# controller3.net
KiCad netlist of a schematic drawn in EAGLE
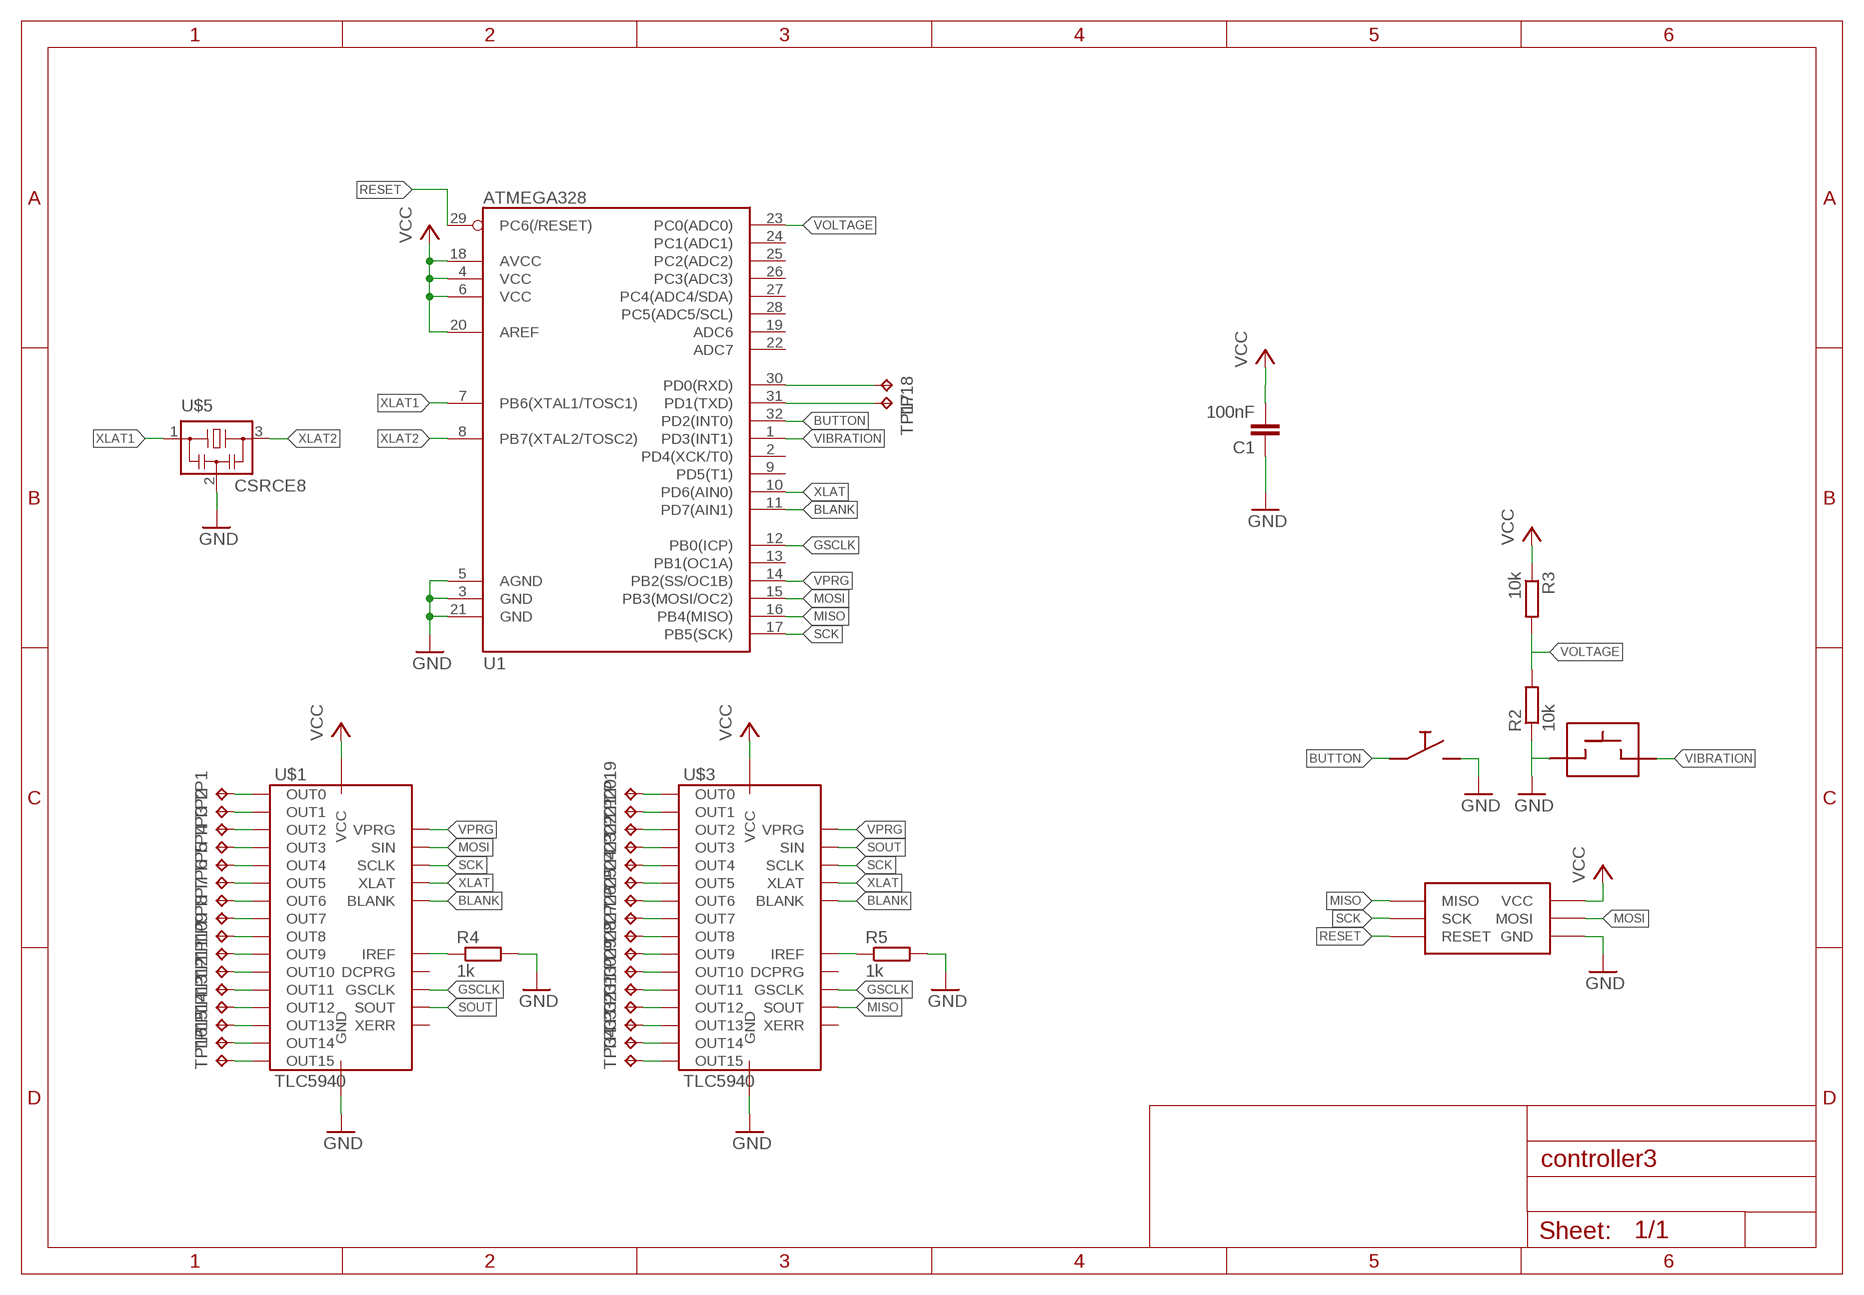
[diagram p0: schematic, sheet 1]

(export (version "E")
  (design (tool "Eeschema 10.0.6"))
  (components
    (comp (ref "C1")
      (value "100nF")
      (footprint "eagle-import:C0603")
      (libsource (lib "eagle-import") (part "C-EUC0603"))
    )
    (comp (ref "R2")
      (value "10k")
      (footprint "eagle-import:R0603")
      (libsource (lib "eagle-import") (part "R-EU_R0603"))
    )
    (comp (ref "R3")
      (value "10k")
      (footprint "eagle-import:R0603")
      (libsource (lib "eagle-import") (part "R-EU_R0603"))
    )
    (comp (ref "R4")
      (value "1k")
      (footprint "eagle-import:R0603")
      (libsource (lib "eagle-import") (part "R-EU_R0603"))
    )
    (comp (ref "R5")
      (value "1k")
      (footprint "eagle-import:R0603")
      (libsource (lib "eagle-import") (part "R-EU_R0603"))
    )
    (comp (ref "TP1")
      (value "TPTP15SQ")
      (footprint "eagle-import:TP15SQ")
      (libsource (lib "eagle-import") (part "TPTP15SQ"))
    )
    (comp (ref "TP2")
      (value "TPTP15SQ")
      (footprint "eagle-import:TP15SQ")
      (libsource (lib "eagle-import") (part "TPTP15SQ"))
    )
    (comp (ref "TP3")
      (value "TPTP15SQ")
      (footprint "eagle-import:TP15SQ")
      (libsource (lib "eagle-import") (part "TPTP15SQ"))
    )
    (comp (ref "TP4")
      (value "TPTP15SQ")
      (footprint "eagle-import:TP15SQ")
      (libsource (lib "eagle-import") (part "TPTP15SQ"))
    )
    (comp (ref "TP5")
      (value "TPTP15SQ")
      (footprint "eagle-import:TP15SQ")
      (libsource (lib "eagle-import") (part "TPTP15SQ"))
    )
    (comp (ref "TP6")
      (value "TPTP15SQ")
      (footprint "eagle-import:TP15SQ")
      (libsource (lib "eagle-import") (part "TPTP15SQ"))
    )
    (comp (ref "TP7")
      (value "TPTP15SQ")
      (footprint "eagle-import:TP15SQ")
      (libsource (lib "eagle-import") (part "TPTP15SQ"))
    )
    (comp (ref "TP8")
      (value "TPTP15SQ")
      (footprint "eagle-import:TP15SQ")
      (libsource (lib "eagle-import") (part "TPTP15SQ"))
    )
    (comp (ref "TP9")
      (value "TPTP15SQ")
      (footprint "eagle-import:TP15SQ")
      (libsource (lib "eagle-import") (part "TPTP15SQ"))
    )
    (comp (ref "TP10")
      (value "TPTP15SQ")
      (footprint "eagle-import:TP15SQ")
      (libsource (lib "eagle-import") (part "TPTP15SQ"))
    )
    (comp (ref "TP11")
      (value "TPTP15SQ")
      (footprint "eagle-import:TP15SQ")
      (libsource (lib "eagle-import") (part "TPTP15SQ"))
    )
    (comp (ref "TP12")
      (value "TPTP15SQ")
      (footprint "eagle-import:TP15SQ")
      (libsource (lib "eagle-import") (part "TPTP15SQ"))
    )
    (comp (ref "TP13")
      (value "TPTP15SQ")
      (footprint "eagle-import:TP15SQ")
      (libsource (lib "eagle-import") (part "TPTP15SQ"))
    )
    (comp (ref "TP14")
      (value "TPTP15SQ")
      (footprint "eagle-import:TP15SQ")
      (libsource (lib "eagle-import") (part "TPTP15SQ"))
    )
    (comp (ref "TP15")
      (value "TPTP15SQ")
      (footprint "eagle-import:TP15SQ")
      (libsource (lib "eagle-import") (part "TPTP15SQ"))
    )
    (comp (ref "TP16")
      (value "TPTP15SQ")
      (footprint "eagle-import:TP15SQ")
      (libsource (lib "eagle-import") (part "TPTP15SQ"))
    )
    (comp (ref "TP17")
      (value "TPTP15SQ")
      (footprint "eagle-import:TP15SQ")
      (libsource (lib "eagle-import") (part "TPTP15SQ"))
    )
    (comp (ref "TP18")
      (value "TPTP15SQ")
      (footprint "eagle-import:TP15SQ")
      (libsource (lib "eagle-import") (part "TPTP15SQ"))
    )
    (comp (ref "TP19")
      (value "TPTP15SQ")
      (footprint "eagle-import:TP15SQ")
      (libsource (lib "eagle-import") (part "TPTP15SQ"))
    )
    (comp (ref "TP20")
      (value "TPTP15SQ")
      (footprint "eagle-import:TP15SQ")
      (libsource (lib "eagle-import") (part "TPTP15SQ"))
    )
    (comp (ref "TP21")
      (value "TPTP15SQ")
      (footprint "eagle-import:TP15SQ")
      (libsource (lib "eagle-import") (part "TPTP15SQ"))
    )
    (comp (ref "TP22")
      (value "TPTP15SQ")
      (footprint "eagle-import:TP15SQ")
      (libsource (lib "eagle-import") (part "TPTP15SQ"))
    )
    (comp (ref "TP23")
      (value "TPTP15SQ")
      (footprint "eagle-import:TP15SQ")
      (libsource (lib "eagle-import") (part "TPTP15SQ"))
    )
    (comp (ref "TP24")
      (value "TPTP15SQ")
      (footprint "eagle-import:TP15SQ")
      (libsource (lib "eagle-import") (part "TPTP15SQ"))
    )
    (comp (ref "TP25")
      (value "TPTP15SQ")
      (footprint "eagle-import:TP15SQ")
      (libsource (lib "eagle-import") (part "TPTP15SQ"))
    )
    (comp (ref "TP26")
      (value "TPTP15SQ")
      (footprint "eagle-import:TP15SQ")
      (libsource (lib "eagle-import") (part "TPTP15SQ"))
    )
    (comp (ref "TP27")
      (value "TPTP15SQ")
      (footprint "eagle-import:TP15SQ")
      (libsource (lib "eagle-import") (part "TPTP15SQ"))
    )
    (comp (ref "TP28")
      (value "TPTP15SQ")
      (footprint "eagle-import:TP15SQ")
      (libsource (lib "eagle-import") (part "TPTP15SQ"))
    )
    (comp (ref "TP29")
      (value "TPTP15SQ")
      (footprint "eagle-import:TP15SQ")
      (libsource (lib "eagle-import") (part "TPTP15SQ"))
    )
    (comp (ref "TP30")
      (value "TPTP15SQ")
      (footprint "eagle-import:TP15SQ")
      (libsource (lib "eagle-import") (part "TPTP15SQ"))
    )
    (comp (ref "TP31")
      (value "TPTP15SQ")
      (footprint "eagle-import:TP15SQ")
      (libsource (lib "eagle-import") (part "TPTP15SQ"))
    )
    (comp (ref "TP32")
      (value "TPTP15SQ")
      (footprint "eagle-import:TP15SQ")
      (libsource (lib "eagle-import") (part "TPTP15SQ"))
    )
    (comp (ref "TP33")
      (value "TPTP15SQ")
      (footprint "eagle-import:TP15SQ")
      (libsource (lib "eagle-import") (part "TPTP15SQ"))
    )
    (comp (ref "TP34")
      (value "TPTP15SQ")
      (footprint "eagle-import:TP15SQ")
      (libsource (lib "eagle-import") (part "TPTP15SQ"))
    )
    (comp (ref "U$1")
      (value "TLC5940")
      (footprint "eagle-import:PWP_28PIN")
      (libsource (lib "eagle-import") (part "TLC5940"))
    )
    (comp (ref "U$2")
      (value "ISP_SPECIALS")
      (footprint "eagle-import:ISP_RM2_00_STRAIGHT")
      (libsource (lib "eagle-import") (part "ISP_SPECIALS"))
    )
    (comp (ref "U$3")
      (value "TLC5940")
      (footprint "eagle-import:PWP_28PIN")
      (libsource (lib "eagle-import") (part "TLC5940"))
    )
    (comp (ref "U$4")
      (value "MOTION_SENSOR")
      (footprint "eagle-import:MOTION")
      (libsource (lib "eagle-import") (part "MOTION_SENSOR"))
    )
    (comp (ref "U$5")
      (value "CSRCE8")
      (footprint "eagle-import:CSTCE_G")
      (libsource (lib "eagle-import") (part "CSRCE8"))
    )
    (comp (ref "U$6")
      (value "SWITCH")
      (footprint "eagle-import:EVQPSG02K")
      (libsource (lib "eagle-import") (part "SWITCH"))
    )
    (comp (ref "U1")
      (value "ATMEGA328")
      (footprint "eagle-import:TQFP32-08")
      (libsource (lib "eagle-import") (part "ATMEGA328"))
    )
  )
  (nets
    (net (code "1") (name "BLANK") (class "Default")
      (node (ref "U$1") (pin "P2") (pinfunction "BLANK_P2") (pintype "input"))
      (node (ref "U$3") (pin "P2") (pinfunction "BLANK_P2") (pintype "input"))
      (node (ref "U1") (pin "11") (pinfunction "PD7(AIN1)_11") (pintype "bidirectional"))
    )
    (net (code "2") (name "BUTTON") (class "Default")
      (node (ref "U$6") (pin "A") (pinfunction "P$1_A") (pintype "bidirectional"))
      (node (ref "U$6") (pin "A@2") (pinfunction "P$1_A@2") (pintype "bidirectional"))
      (node (ref "U1") (pin "32") (pinfunction "PD2(INT0)_32") (pintype "bidirectional"))
    )
    (net (code "3") (name "GND") (class "Default")
      (node (ref "C1") (pin "1") (pinfunction "1_1") (pintype "passive"))
      (node (ref "R2") (pin "1") (pinfunction "1_1") (pintype "passive"))
      (node (ref "R4") (pin "2") (pinfunction "2_2") (pintype "passive"))
      (node (ref "R5") (pin "2") (pinfunction "2_2") (pintype "passive"))
      (node (ref "U$1") (pin "P1") (pinfunction "GND_P1") (pintype "power_in"))
      (node (ref "U$1") (pin "P29") (pinfunction "GND_P29") (pintype "power_in"))
      (node (ref "U$2") (pin "VCC") (pinfunction "GND_VCC") (pintype "bidirectional"))
      (node (ref "U$3") (pin "P1") (pinfunction "GND_P1") (pintype "power_in"))
      (node (ref "U$3") (pin "P29") (pinfunction "GND_P29") (pintype "power_in"))
      (node (ref "U$4") (pin "P$1") (pinfunction "IN_P$1") (pintype "bidirectional"))
      (node (ref "U$5") (pin "2") (pinfunction "2_2") (pintype "passive"))
      (node (ref "U$6") (pin "B") (pinfunction "P$2_B") (pintype "bidirectional"))
      (node (ref "U$6") (pin "B@2") (pinfunction "P$2_B@2") (pintype "bidirectional"))
      (node (ref "U1") (pin "21") (pinfunction "GND_21") (pintype "bidirectional"))
      (node (ref "U1") (pin "3") (pinfunction "GND_3") (pintype "bidirectional"))
      (node (ref "U1") (pin "5") (pinfunction "AGND_5") (pintype "bidirectional"))
    )
    (net (code "4") (name "GSCLK") (class "Default")
      (node (ref "U$1") (pin "P25") (pinfunction "GSCLK_P25") (pintype "input"))
      (node (ref "U$3") (pin "P25") (pinfunction "GSCLK_P25") (pintype "input"))
      (node (ref "U1") (pin "12") (pinfunction "PB0(ICP)_12") (pintype "bidirectional"))
    )
    (net (code "5") (name "MISO") (class "Default")
      (node (ref "U$2") (pin "RESET") (pinfunction "MISO_RESET") (pintype "bidirectional"))
      (node (ref "U$3") (pin "P24") (pinfunction "SOUT_P24") (pintype "output"))
      (node (ref "U1") (pin "16") (pinfunction "PB4(MISO)_16") (pintype "bidirectional"))
    )
    (net (code "6") (name "MOSI") (class "Default")
      (node (ref "U$1") (pin "P5") (pinfunction "SIN_P5") (pintype "input"))
      (node (ref "U$2") (pin "MOSI") (pinfunction "MOSI_MOSI") (pintype "bidirectional"))
      (node (ref "U1") (pin "15") (pinfunction "PB3(MOSI/OC2)_15") (pintype "bidirectional"))
    )
    (net (code "7") (name "Net-(U$1-IREF)") (class "Default")
      (node (ref "R4") (pin "1") (pinfunction "1_1") (pintype "passive"))
      (node (ref "U$1") (pin "P27") (pinfunction "IREF_P27") (pintype "passive"))
    )
    (net (code "8") (name "Net-(U$1-OUT0)") (class "Default")
      (node (ref "TP1") (pin "TP") (pinfunction "TP_TP") (pintype "input"))
      (node (ref "U$1") (pin "P7") (pinfunction "OUT0_P7") (pintype "open_collector"))
    )
    (net (code "9") (name "Net-(U$1-OUT1)") (class "Default")
      (node (ref "TP2") (pin "TP") (pinfunction "TP_TP") (pintype "input"))
      (node (ref "U$1") (pin "P8") (pinfunction "OUT1_P8") (pintype "open_collector"))
    )
    (net (code "10") (name "Net-(U$1-OUT2)") (class "Default")
      (node (ref "TP3") (pin "TP") (pinfunction "TP_TP") (pintype "input"))
      (node (ref "U$1") (pin "P9") (pinfunction "OUT2_P9") (pintype "open_collector"))
    )
    (net (code "11") (name "Net-(U$1-OUT3)") (class "Default")
      (node (ref "TP4") (pin "TP") (pinfunction "TP_TP") (pintype "input"))
      (node (ref "U$1") (pin "P10") (pinfunction "OUT3_P10") (pintype "open_collector"))
    )
    (net (code "12") (name "Net-(U$1-OUT4)") (class "Default")
      (node (ref "TP5") (pin "TP") (pinfunction "TP_TP") (pintype "input"))
      (node (ref "U$1") (pin "P11") (pinfunction "OUT4_P11") (pintype "open_collector"))
    )
    (net (code "13") (name "Net-(U$1-OUT5)") (class "Default")
      (node (ref "TP6") (pin "TP") (pinfunction "TP_TP") (pintype "input"))
      (node (ref "U$1") (pin "P12") (pinfunction "OUT5_P12") (pintype "open_collector"))
    )
    (net (code "14") (name "Net-(U$1-OUT6)") (class "Default")
      (node (ref "TP7") (pin "TP") (pinfunction "TP_TP") (pintype "input"))
      (node (ref "U$1") (pin "P13") (pinfunction "OUT6_P13") (pintype "open_collector"))
    )
    (net (code "15") (name "Net-(U$1-OUT7)") (class "Default")
      (node (ref "TP8") (pin "TP") (pinfunction "TP_TP") (pintype "input"))
      (node (ref "U$1") (pin "P14") (pinfunction "OUT7_P14") (pintype "open_collector"))
    )
    (net (code "16") (name "Net-(U$1-OUT8)") (class "Default")
      (node (ref "TP9") (pin "TP") (pinfunction "TP_TP") (pintype "input"))
      (node (ref "U$1") (pin "P15") (pinfunction "OUT8_P15") (pintype "open_collector"))
    )
    (net (code "17") (name "Net-(U$1-OUT9)") (class "Default")
      (node (ref "TP10") (pin "TP") (pinfunction "TP_TP") (pintype "input"))
      (node (ref "U$1") (pin "P16") (pinfunction "OUT9_P16") (pintype "open_collector"))
    )
    (net (code "18") (name "Net-(U$1-OUT10)") (class "Default")
      (node (ref "TP11") (pin "TP") (pinfunction "TP_TP") (pintype "input"))
      (node (ref "U$1") (pin "P17") (pinfunction "OUT10_P17") (pintype "open_collector"))
    )
    (net (code "19") (name "Net-(U$1-OUT11)") (class "Default")
      (node (ref "TP12") (pin "TP") (pinfunction "TP_TP") (pintype "input"))
      (node (ref "U$1") (pin "P18") (pinfunction "OUT11_P18") (pintype "open_collector"))
    )
    (net (code "20") (name "Net-(U$1-OUT12)") (class "Default")
      (node (ref "TP13") (pin "TP") (pinfunction "TP_TP") (pintype "input"))
      (node (ref "U$1") (pin "P19") (pinfunction "OUT12_P19") (pintype "open_collector"))
    )
    (net (code "21") (name "Net-(U$1-OUT13)") (class "Default")
      (node (ref "TP14") (pin "TP") (pinfunction "TP_TP") (pintype "input"))
      (node (ref "U$1") (pin "P20") (pinfunction "OUT13_P20") (pintype "open_collector"))
    )
    (net (code "22") (name "Net-(U$1-OUT14)") (class "Default")
      (node (ref "TP15") (pin "TP") (pinfunction "TP_TP") (pintype "input"))
      (node (ref "U$1") (pin "P21") (pinfunction "OUT14_P21") (pintype "open_collector"))
    )
    (net (code "23") (name "Net-(U$1-OUT15)") (class "Default")
      (node (ref "TP16") (pin "TP") (pinfunction "TP_TP") (pintype "input"))
      (node (ref "U$1") (pin "P22") (pinfunction "OUT15_P22") (pintype "open_collector"))
    )
    (net (code "24") (name "Net-(U$3-IREF)") (class "Default")
      (node (ref "R5") (pin "1") (pinfunction "1_1") (pintype "passive"))
      (node (ref "U$3") (pin "P27") (pinfunction "IREF_P27") (pintype "passive"))
    )
    (net (code "25") (name "Net-(U$3-OUT0)") (class "Default")
      (node (ref "TP19") (pin "TP") (pinfunction "TP_TP") (pintype "input"))
      (node (ref "U$3") (pin "P7") (pinfunction "OUT0_P7") (pintype "open_collector"))
    )
    (net (code "26") (name "Net-(U$3-OUT1)") (class "Default")
      (node (ref "TP20") (pin "TP") (pinfunction "TP_TP") (pintype "input"))
      (node (ref "U$3") (pin "P8") (pinfunction "OUT1_P8") (pintype "open_collector"))
    )
    (net (code "27") (name "Net-(U$3-OUT2)") (class "Default")
      (node (ref "TP21") (pin "TP") (pinfunction "TP_TP") (pintype "input"))
      (node (ref "U$3") (pin "P9") (pinfunction "OUT2_P9") (pintype "open_collector"))
    )
    (net (code "28") (name "Net-(U$3-OUT3)") (class "Default")
      (node (ref "TP22") (pin "TP") (pinfunction "TP_TP") (pintype "input"))
      (node (ref "U$3") (pin "P10") (pinfunction "OUT3_P10") (pintype "open_collector"))
    )
    (net (code "29") (name "Net-(U$3-OUT4)") (class "Default")
      (node (ref "TP23") (pin "TP") (pinfunction "TP_TP") (pintype "input"))
      (node (ref "U$3") (pin "P11") (pinfunction "OUT4_P11") (pintype "open_collector"))
    )
    (net (code "30") (name "Net-(U$3-OUT5)") (class "Default")
      (node (ref "TP24") (pin "TP") (pinfunction "TP_TP") (pintype "input"))
      (node (ref "U$3") (pin "P12") (pinfunction "OUT5_P12") (pintype "open_collector"))
    )
    (net (code "31") (name "Net-(U$3-OUT6)") (class "Default")
      (node (ref "TP25") (pin "TP") (pinfunction "TP_TP") (pintype "input"))
      (node (ref "U$3") (pin "P13") (pinfunction "OUT6_P13") (pintype "open_collector"))
    )
    (net (code "32") (name "Net-(U$3-OUT7)") (class "Default")
      (node (ref "TP26") (pin "TP") (pinfunction "TP_TP") (pintype "input"))
      (node (ref "U$3") (pin "P14") (pinfunction "OUT7_P14") (pintype "open_collector"))
    )
    (net (code "33") (name "Net-(U$3-OUT8)") (class "Default")
      (node (ref "TP27") (pin "TP") (pinfunction "TP_TP") (pintype "input"))
      (node (ref "U$3") (pin "P15") (pinfunction "OUT8_P15") (pintype "open_collector"))
    )
    (net (code "34") (name "Net-(U$3-OUT9)") (class "Default")
      (node (ref "TP28") (pin "TP") (pinfunction "TP_TP") (pintype "input"))
      (node (ref "U$3") (pin "P16") (pinfunction "OUT9_P16") (pintype "open_collector"))
    )
    (net (code "35") (name "Net-(U$3-OUT10)") (class "Default")
      (node (ref "TP29") (pin "TP") (pinfunction "TP_TP") (pintype "input"))
      (node (ref "U$3") (pin "P17") (pinfunction "OUT10_P17") (pintype "open_collector"))
    )
    (net (code "36") (name "Net-(U$3-OUT11)") (class "Default")
      (node (ref "TP30") (pin "TP") (pinfunction "TP_TP") (pintype "input"))
      (node (ref "U$3") (pin "P18") (pinfunction "OUT11_P18") (pintype "open_collector"))
    )
    (net (code "37") (name "Net-(U$3-OUT12)") (class "Default")
      (node (ref "TP31") (pin "TP") (pinfunction "TP_TP") (pintype "input"))
      (node (ref "U$3") (pin "P19") (pinfunction "OUT12_P19") (pintype "open_collector"))
    )
    (net (code "38") (name "Net-(U$3-OUT13)") (class "Default")
      (node (ref "TP32") (pin "TP") (pinfunction "TP_TP") (pintype "input"))
      (node (ref "U$3") (pin "P20") (pinfunction "OUT13_P20") (pintype "open_collector"))
    )
    (net (code "39") (name "Net-(U$3-OUT14)") (class "Default")
      (node (ref "TP33") (pin "TP") (pinfunction "TP_TP") (pintype "input"))
      (node (ref "U$3") (pin "P21") (pinfunction "OUT14_P21") (pintype "open_collector"))
    )
    (net (code "40") (name "Net-(U$3-OUT15)") (class "Default")
      (node (ref "TP34") (pin "TP") (pinfunction "TP_TP") (pintype "input"))
      (node (ref "U$3") (pin "P22") (pinfunction "OUT15_P22") (pintype "open_collector"))
    )
    (net (code "41") (name "Net-(U1-PD0(RXD))") (class "Default")
      (node (ref "TP18") (pin "TP") (pinfunction "TP_TP") (pintype "input"))
      (node (ref "U1") (pin "30") (pinfunction "PD0(RXD)_30") (pintype "bidirectional"))
    )
    (net (code "42") (name "Net-(U1-PD1(TXD))") (class "Default")
      (node (ref "TP17") (pin "TP") (pinfunction "TP_TP") (pintype "input"))
      (node (ref "U1") (pin "31") (pinfunction "PD1(TXD)_31") (pintype "bidirectional"))
    )
    (net (code "43") (name "RESET") (class "Default")
      (node (ref "U$2") (pin "MISO") (pinfunction "RESET_MISO") (pintype "bidirectional"))
      (node (ref "U1") (pin "29") (pinfunction "PC6(/RESET)_29") (pintype "bidirectional"))
    )
    (net (code "44") (name "SCK") (class "Default")
      (node (ref "U$1") (pin "P4") (pinfunction "SCLK_P4") (pintype "input"))
      (node (ref "U$2") (pin "SCK") (pinfunction "SCK_SCK") (pintype "bidirectional"))
      (node (ref "U$3") (pin "P4") (pinfunction "SCLK_P4") (pintype "input"))
      (node (ref "U1") (pin "17") (pinfunction "PB5(SCK)_17") (pintype "bidirectional"))
    )
    (net (code "45") (name "SOUT") (class "Default")
      (node (ref "U$1") (pin "P24") (pinfunction "SOUT_P24") (pintype "output"))
      (node (ref "U$3") (pin "P5") (pinfunction "SIN_P5") (pintype "input"))
    )
    (net (code "46") (name "VCC") (class "Default")
      (node (ref "C1") (pin "2") (pinfunction "2_2") (pintype "passive"))
      (node (ref "R3") (pin "1") (pinfunction "1_1") (pintype "passive"))
      (node (ref "U$1") (pin "P28") (pinfunction "VCC_P28") (pintype "power_in"))
      (node (ref "U$2") (pin "GND") (pinfunction "VCC_GND") (pintype "bidirectional"))
      (node (ref "U$3") (pin "P28") (pinfunction "VCC_P28") (pintype "power_in"))
      (node (ref "U1") (pin "18") (pinfunction "AVCC_18") (pintype "bidirectional"))
      (node (ref "U1") (pin "20") (pinfunction "AREF_20") (pintype "bidirectional"))
      (node (ref "U1") (pin "4") (pinfunction "VCC_4") (pintype "bidirectional"))
      (node (ref "U1") (pin "6") (pinfunction "VCC_6") (pintype "bidirectional"))
    )
    (net (code "47") (name "VIBRATION") (class "Default")
      (node (ref "U$4") (pin "P$2") (pinfunction "OUT_P$2") (pintype "bidirectional"))
      (node (ref "U1") (pin "1") (pinfunction "PD3(INT1)_1") (pintype "bidirectional"))
    )
    (net (code "48") (name "VOLTAGE") (class "Default")
      (node (ref "R2") (pin "2") (pinfunction "2_2") (pintype "passive"))
      (node (ref "R3") (pin "2") (pinfunction "2_2") (pintype "passive"))
      (node (ref "U1") (pin "23") (pinfunction "PC0(ADC0)_23") (pintype "bidirectional"))
    )
    (net (code "49") (name "VPRG") (class "Default")
      (node (ref "U$1") (pin "P6") (pinfunction "VPRG_P6") (pintype "input"))
      (node (ref "U$3") (pin "P6") (pinfunction "VPRG_P6") (pintype "input"))
      (node (ref "U1") (pin "14") (pinfunction "PB2(SS/OC1B)_14") (pintype "bidirectional"))
    )
    (net (code "50") (name "XLAT") (class "Default")
      (node (ref "U$1") (pin "P3") (pinfunction "XLAT_P3") (pintype "input"))
      (node (ref "U$3") (pin "P3") (pinfunction "XLAT_P3") (pintype "input"))
      (node (ref "U1") (pin "10") (pinfunction "PD6(AIN0)_10") (pintype "bidirectional"))
    )
    (net (code "51") (name "XLAT1") (class "Default")
      (node (ref "U$5") (pin "1") (pinfunction "1_1") (pintype "passive"))
      (node (ref "U1") (pin "7") (pinfunction "PB6(XTAL1/TOSC1)_7") (pintype "bidirectional"))
    )
    (net (code "52") (name "XLAT2") (class "Default")
      (node (ref "U$5") (pin "3") (pinfunction "3_3") (pintype "passive"))
      (node (ref "U1") (pin "8") (pinfunction "PB7(XTAL2/TOSC2)_8") (pintype "bidirectional"))
    )
    (net (code "53") (name "unconnected-(U$1-DCPRG-PadP26)") (class "Default")
      (node (ref "U$1") (pin "P26") (pinfunction "DCPRG_P26") (pintype "input"))
    )
    (net (code "54") (name "unconnected-(U$1-XERR-PadP23)") (class "Default")
      (node (ref "U$1") (pin "P23") (pinfunction "XERR_P23") (pintype "open_collector"))
    )
    (net (code "55") (name "unconnected-(U$3-DCPRG-PadP26)") (class "Default")
      (node (ref "U$3") (pin "P26") (pinfunction "DCPRG_P26") (pintype "input"))
    )
    (net (code "56") (name "unconnected-(U$3-XERR-PadP23)") (class "Default")
      (node (ref "U$3") (pin "P23") (pinfunction "XERR_P23") (pintype "open_collector"))
    )
    (net (code "57") (name "unconnected-(U1-ADC6-Pad19)") (class "Default")
      (node (ref "U1") (pin "19") (pinfunction "ADC6_19") (pintype "bidirectional"))
    )
    (net (code "58") (name "unconnected-(U1-ADC7-Pad22)") (class "Default")
      (node (ref "U1") (pin "22") (pinfunction "ADC7_22") (pintype "bidirectional"))
    )
    (net (code "59") (name "unconnected-(U1-PB1(OC1A)-Pad13)") (class "Default")
      (node (ref "U1") (pin "13") (pinfunction "PB1(OC1A)_13") (pintype "bidirectional"))
    )
    (net (code "60") (name "unconnected-(U1-PC1(ADC1)-Pad24)") (class "Default")
      (node (ref "U1") (pin "24") (pinfunction "PC1(ADC1)_24") (pintype "bidirectional"))
    )
    (net (code "61") (name "unconnected-(U1-PC2(ADC2)-Pad25)") (class "Default")
      (node (ref "U1") (pin "25") (pinfunction "PC2(ADC2)_25") (pintype "bidirectional"))
    )
    (net (code "62") (name "unconnected-(U1-PC3(ADC3)-Pad26)") (class "Default")
      (node (ref "U1") (pin "26") (pinfunction "PC3(ADC3)_26") (pintype "bidirectional"))
    )
    (net (code "63") (name "unconnected-(U1-PC4(ADC4{slash}SDA)-Pad27)") (class "Default")
      (node (ref "U1") (pin "27") (pinfunction "PC4(ADC4/SDA)_27") (pintype "bidirectional"))
    )
    (net (code "64") (name "unconnected-(U1-PC5(ADC5{slash}SCL)-Pad28)") (class "Default")
      (node (ref "U1") (pin "28") (pinfunction "PC5(ADC5/SCL)_28") (pintype "bidirectional"))
    )
    (net (code "65") (name "unconnected-(U1-PD4(XCK{slash}T0)-Pad2)") (class "Default")
      (node (ref "U1") (pin "2") (pinfunction "PD4(XCK/T0)_2") (pintype "bidirectional"))
    )
    (net (code "66") (name "unconnected-(U1-PD5(T1)-Pad9)") (class "Default")
      (node (ref "U1") (pin "9") (pinfunction "PD5(T1)_9") (pintype "bidirectional"))
    )
  )
)
